# Movimiento.net
KiCad netlist of a schematic drawn in EAGLE
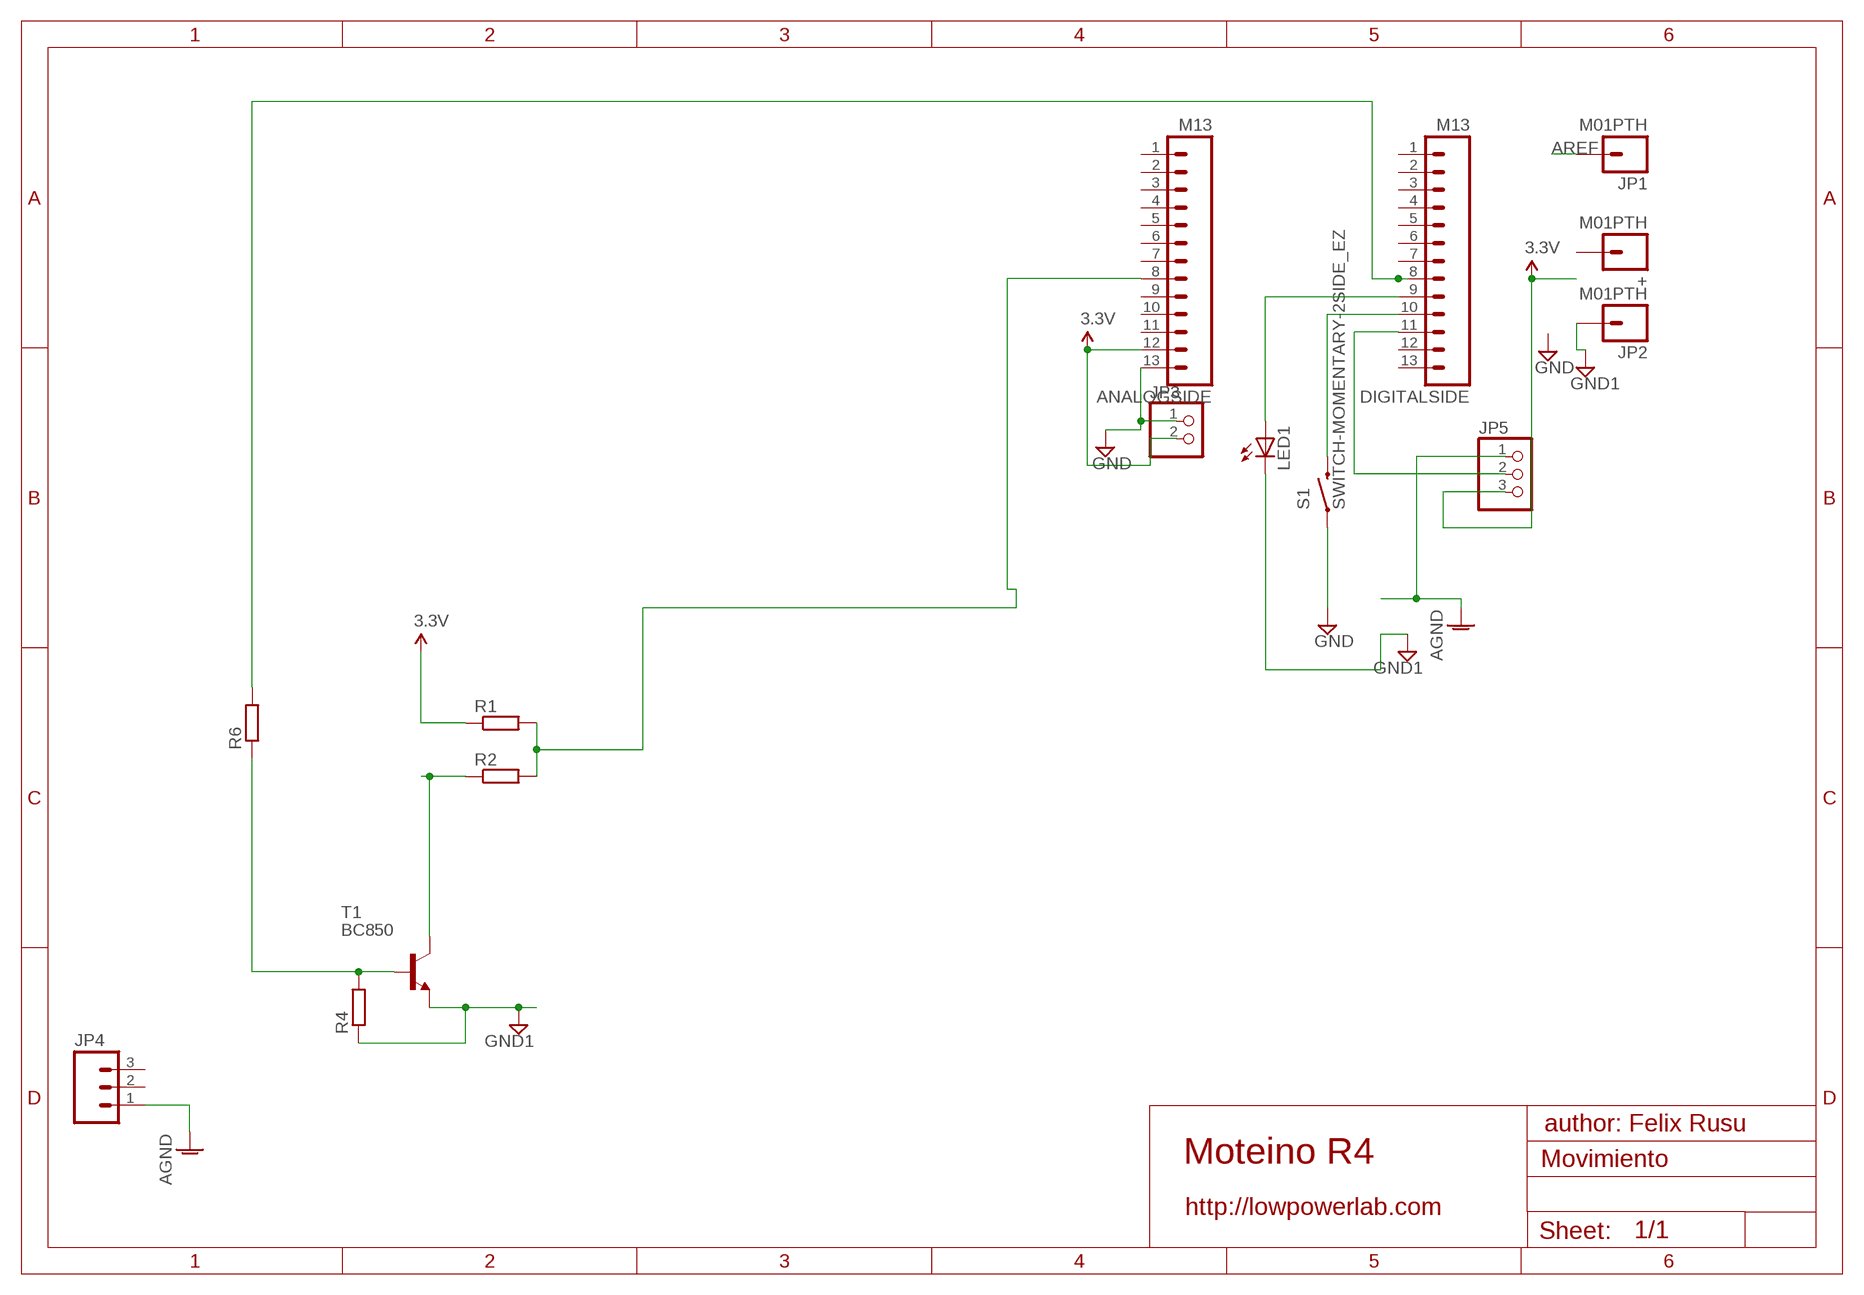
[diagram p0: schematic, sheet 1]

(export (version "E")
  (design (tool "Eeschema 10.0.6"))
  (components
    (comp (ref "+")
      (value "M01PTH")
      (footprint "eagle-import:1X01")
      (libsource (lib "eagle-import") (part "M01PTH"))
    )
    (comp (ref "ANALOGSIDE")
      (value "M13")
      (footprint "eagle-import:1X13")
      (libsource (lib "eagle-import") (part "M13"))
    )
    (comp (ref "DIGITALSIDE")
      (value "M13")
      (footprint "eagle-import:1X13")
      (libsource (lib "eagle-import") (part "M13"))
    )
    (comp (ref "JP1")
      (value "M01PTH")
      (footprint "eagle-import:1X01")
      (libsource (lib "eagle-import") (part "M01PTH"))
    )
    (comp (ref "JP2")
      (value "M01PTH")
      (footprint "eagle-import:1X01")
      (libsource (lib "eagle-import") (part "M01PTH"))
    )
    (comp (ref "JP3")
      (value "PINHD-1X2")
      (footprint "eagle-import:1X02")
      (libsource (lib "eagle-import") (part "PINHD-1X2"))
    )
    (comp (ref "JP4")
      (value "M03PTH")
      (footprint "eagle-import:1X03")
      (libsource (lib "eagle-import") (part "M03PTH"))
    )
    (comp (ref "JP5")
      (value "PINHD-1X3")
      (footprint "eagle-import:1X03")
      (libsource (lib "eagle-import") (part "PINHD-1X3"))
    )
    (comp (ref "LED1")
      (value "LED3MM")
      (footprint "eagle-import:LED3MM")
      (libsource (lib "eagle-import") (part "LED3MM"))
    )
    (comp (ref "R1")
      (value "R-EU_0204/7")
      (footprint "eagle-import:0204_7")
      (libsource (lib "eagle-import") (part "R-EU_0204/7"))
    )
    (comp (ref "R2")
      (value "R-EU_0204/7")
      (footprint "eagle-import:0204_7")
      (libsource (lib "eagle-import") (part "R-EU_0204/7"))
    )
    (comp (ref "R4")
      (value "R-EU_M1206")
      (footprint "eagle-import:M1206")
      (libsource (lib "eagle-import") (part "R-EU_M1206"))
    )
    (comp (ref "R6")
      (value "R-EU_M1206")
      (footprint "eagle-import:M1206")
      (libsource (lib "eagle-import") (part "R-EU_M1206"))
    )
    (comp (ref "S1")
      (value "SWITCH-MOMENTARY-2SIDE_EZ")
      (footprint "eagle-import:TACTILE-PTH-SIDEEZ")
      (libsource (lib "eagle-import") (part "SWITCH-MOMENTARY-2SIDE_EZ"))
    )
    (comp (ref "T1")
      (value "BC850")
      (footprint "eagle-import:SOT23")
      (libsource (lib "eagle-import") (part "BC850"))
    )
  )
  (nets
    (net (code "1") (name "/AREF") (class "Default")
      (node (ref "JP1") (pin "1") (pinfunction "1_1") (pintype "passive"))
    )
    (net (code "2") (name "3.3V") (class "Default")
      (node (ref "ANALOGSIDE") (pin "12") (pinfunction "12_12") (pintype "passive"))
      (node (ref "JP3") (pin "2") (pinfunction "2_2") (pintype "passive"))
      (node (ref "JP5") (pin "3") (pinfunction "3_3") (pintype "passive"))
      (node (ref "R1") (pin "1") (pinfunction "1_1") (pintype "passive"))
    )
    (net (code "3") (name "AGND") (class "Default")
      (node (ref "JP4") (pin "1") (pinfunction "1_1") (pintype "passive"))
      (node (ref "JP5") (pin "1") (pinfunction "1_1") (pintype "passive"))
    )
    (net (code "4") (name "GND") (class "Default")
      (node (ref "ANALOGSIDE") (pin "13") (pinfunction "13_13") (pintype "passive"))
      (node (ref "JP3") (pin "1") (pinfunction "1_1") (pintype "passive"))
      (node (ref "S1") (pin "1") (pinfunction "1_1") (pintype "passive"))
    )
    (net (code "5") (name "GND1") (class "Default")
      (node (ref "JP2") (pin "1") (pinfunction "1_1") (pintype "passive"))
      (node (ref "LED1") (pin "K") (pinfunction "C_K") (pintype "passive"))
      (node (ref "R4") (pin "1") (pinfunction "1_1") (pintype "passive"))
      (node (ref "T1") (pin "2") (pinfunction "E_2") (pintype "passive"))
    )
    (net (code "6") (name "Net-(ANALOGSIDE-Pad8)") (class "Default")
      (node (ref "ANALOGSIDE") (pin "8") (pinfunction "8_8") (pintype "passive"))
      (node (ref "R1") (pin "2") (pinfunction "2_2") (pintype "passive"))
      (node (ref "R2") (pin "2") (pinfunction "2_2") (pintype "passive"))
    )
    (net (code "7") (name "Net-(DIGITALSIDE-Pad8)") (class "Default")
      (node (ref "DIGITALSIDE") (pin "8") (pinfunction "8_8") (pintype "passive"))
      (node (ref "R6") (pin "2") (pinfunction "2_2") (pintype "passive"))
    )
    (net (code "8") (name "Net-(DIGITALSIDE-Pad9)") (class "Default")
      (node (ref "DIGITALSIDE") (pin "9") (pinfunction "9_9") (pintype "passive"))
      (node (ref "LED1") (pin "A") (pinfunction "A_A") (pintype "passive"))
    )
    (net (code "9") (name "Net-(DIGITALSIDE-Pad10)") (class "Default")
      (node (ref "DIGITALSIDE") (pin "10") (pinfunction "10_10") (pintype "passive"))
      (node (ref "S1") (pin "2") (pinfunction "2_2") (pintype "passive"))
    )
    (net (code "10") (name "Net-(DIGITALSIDE-Pad11)") (class "Default")
      (node (ref "DIGITALSIDE") (pin "11") (pinfunction "11_11") (pintype "passive"))
      (node (ref "JP5") (pin "2") (pinfunction "2_2") (pintype "passive"))
    )
    (net (code "11") (name "Net-(T1-B)") (class "Default")
      (node (ref "R4") (pin "2") (pinfunction "2_2") (pintype "passive"))
      (node (ref "R6") (pin "1") (pinfunction "1_1") (pintype "passive"))
      (node (ref "T1") (pin "1") (pinfunction "B_1") (pintype "passive"))
    )
    (net (code "12") (name "Net-(T1-C)") (class "Default")
      (node (ref "R2") (pin "1") (pinfunction "1_1") (pintype "passive"))
      (node (ref "T1") (pin "3") (pinfunction "C_3") (pintype "passive"))
    )
    (net (code "13") (name "unconnected-(+-Pad1)") (class "Default")
      (node (ref "+") (pin "1") (pinfunction "1_1") (pintype "passive"))
    )
    (net (code "14") (name "unconnected-(ANALOGSIDE-Pad1)") (class "Default")
      (node (ref "ANALOGSIDE") (pin "1") (pinfunction "1_1") (pintype "passive"))
    )
    (net (code "15") (name "unconnected-(ANALOGSIDE-Pad2)") (class "Default")
      (node (ref "ANALOGSIDE") (pin "2") (pinfunction "2_2") (pintype "passive"))
    )
    (net (code "16") (name "unconnected-(ANALOGSIDE-Pad3)") (class "Default")
      (node (ref "ANALOGSIDE") (pin "3") (pinfunction "3_3") (pintype "passive"))
    )
    (net (code "17") (name "unconnected-(ANALOGSIDE-Pad4)") (class "Default")
      (node (ref "ANALOGSIDE") (pin "4") (pinfunction "4_4") (pintype "passive"))
    )
    (net (code "18") (name "unconnected-(ANALOGSIDE-Pad5)") (class "Default")
      (node (ref "ANALOGSIDE") (pin "5") (pinfunction "5_5") (pintype "passive"))
    )
    (net (code "19") (name "unconnected-(ANALOGSIDE-Pad6)") (class "Default")
      (node (ref "ANALOGSIDE") (pin "6") (pinfunction "6_6") (pintype "passive"))
    )
    (net (code "20") (name "unconnected-(ANALOGSIDE-Pad7)") (class "Default")
      (node (ref "ANALOGSIDE") (pin "7") (pinfunction "7_7") (pintype "passive"))
    )
    (net (code "21") (name "unconnected-(ANALOGSIDE-Pad9)") (class "Default")
      (node (ref "ANALOGSIDE") (pin "9") (pinfunction "9_9") (pintype "passive"))
    )
    (net (code "22") (name "unconnected-(ANALOGSIDE-Pad10)") (class "Default")
      (node (ref "ANALOGSIDE") (pin "10") (pinfunction "10_10") (pintype "passive"))
    )
    (net (code "23") (name "unconnected-(ANALOGSIDE-Pad11)") (class "Default")
      (node (ref "ANALOGSIDE") (pin "11") (pinfunction "11_11") (pintype "passive"))
    )
    (net (code "24") (name "unconnected-(DIGITALSIDE-Pad1)") (class "Default")
      (node (ref "DIGITALSIDE") (pin "1") (pinfunction "1_1") (pintype "passive"))
    )
    (net (code "25") (name "unconnected-(DIGITALSIDE-Pad2)") (class "Default")
      (node (ref "DIGITALSIDE") (pin "2") (pinfunction "2_2") (pintype "passive"))
    )
    (net (code "26") (name "unconnected-(DIGITALSIDE-Pad3)") (class "Default")
      (node (ref "DIGITALSIDE") (pin "3") (pinfunction "3_3") (pintype "passive"))
    )
    (net (code "27") (name "unconnected-(DIGITALSIDE-Pad4)") (class "Default")
      (node (ref "DIGITALSIDE") (pin "4") (pinfunction "4_4") (pintype "passive"))
    )
    (net (code "28") (name "unconnected-(DIGITALSIDE-Pad5)") (class "Default")
      (node (ref "DIGITALSIDE") (pin "5") (pinfunction "5_5") (pintype "passive"))
    )
    (net (code "29") (name "unconnected-(DIGITALSIDE-Pad6)") (class "Default")
      (node (ref "DIGITALSIDE") (pin "6") (pinfunction "6_6") (pintype "passive"))
    )
    (net (code "30") (name "unconnected-(DIGITALSIDE-Pad7)") (class "Default")
      (node (ref "DIGITALSIDE") (pin "7") (pinfunction "7_7") (pintype "passive"))
    )
    (net (code "31") (name "unconnected-(DIGITALSIDE-Pad12)") (class "Default")
      (node (ref "DIGITALSIDE") (pin "12") (pinfunction "12_12") (pintype "passive"))
    )
    (net (code "32") (name "unconnected-(DIGITALSIDE-Pad13)") (class "Default")
      (node (ref "DIGITALSIDE") (pin "13") (pinfunction "13_13") (pintype "passive"))
    )
    (net (code "33") (name "unconnected-(JP4-Pad2)") (class "Default")
      (node (ref "JP4") (pin "2") (pinfunction "2_2") (pintype "passive"))
    )
    (net (code "34") (name "unconnected-(JP4-Pad3)") (class "Default")
      (node (ref "JP4") (pin "3") (pinfunction "3_3") (pintype "passive"))
    )
  )
)
